# microlab.net
KiCad netlist of a schematic drawn in Altium Designer
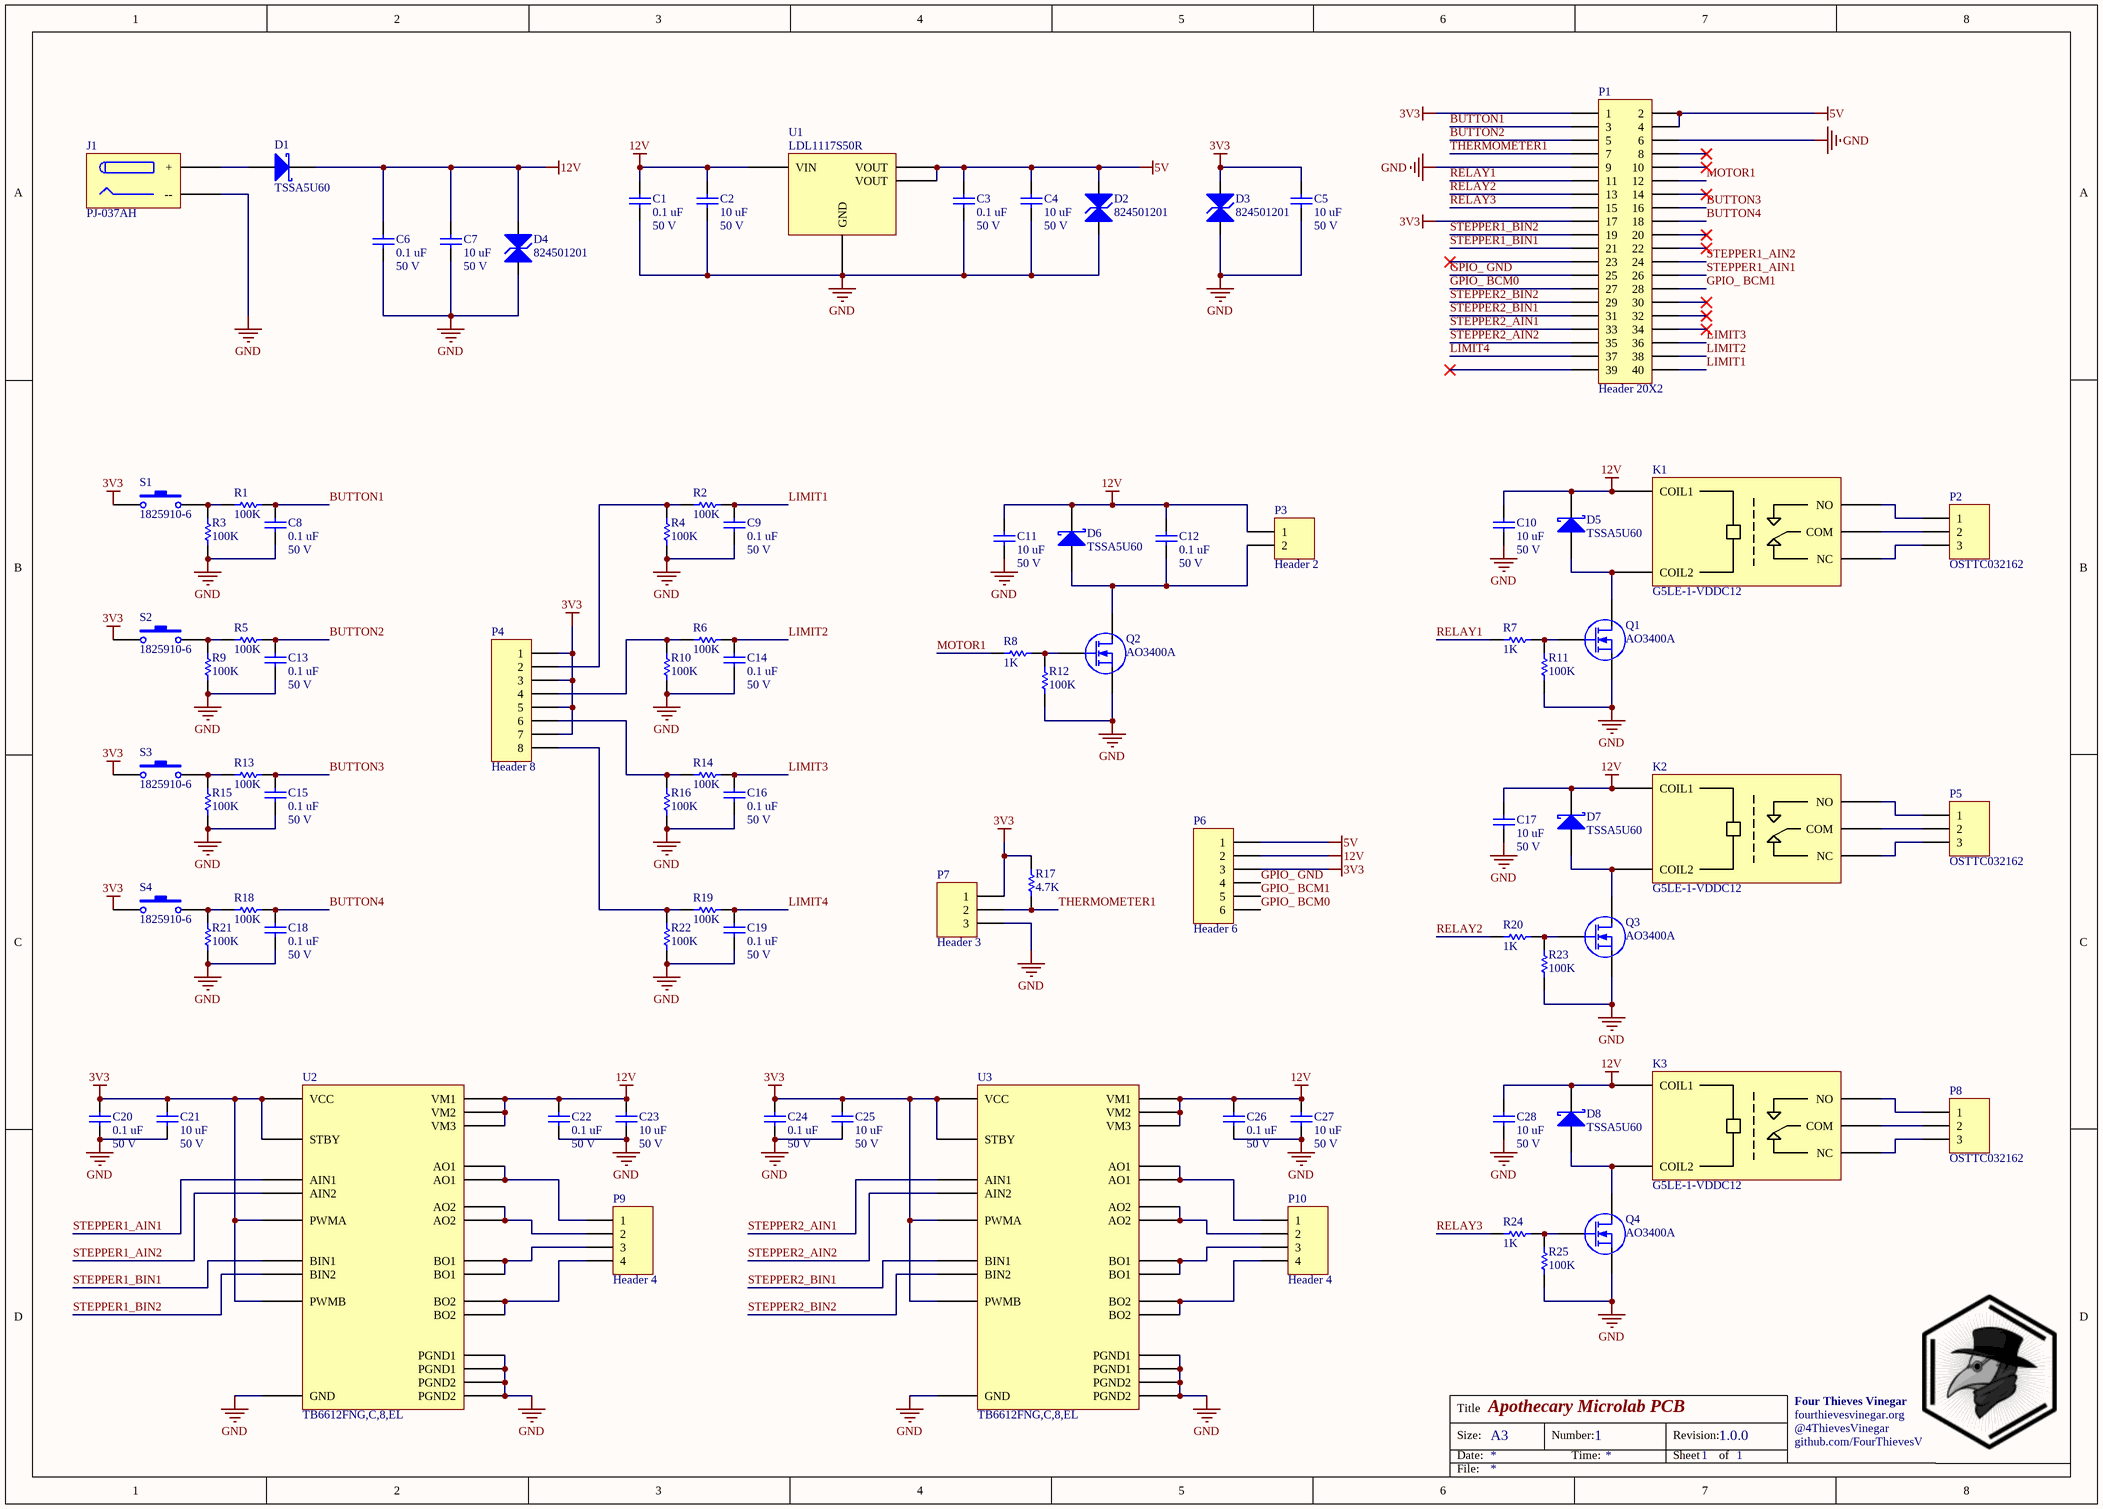
[diagram p0: microlab.SchDoc]

(export (version "E")
  (design (tool "Eeschema 10.0.6"))
  (components
    (comp (ref "C1")
      (value "0.1 uF")
      (footprint "1608[0603]")
      (description "Capacitor (Semiconductor SIM Model)")
      (fields (field (name "VOLTAGE") "50 V") (field (name "PUBLISHER") "Altium Limited"))
      (libsource (lib "Miscellaneous Devices") (part "Cap Semi"))
    )
    (comp (ref "C2")
      (value "10 uF")
      (footprint "C1206")
      (description "CL31A106KBHNNNE")
      (fields (field (name "VOLTAGE") "50 V") (field (name "PUBLISHER") "Altium Limited"))
      (libsource (lib "Miscellaneous Devices") (part "Cap Semi"))
    )
    (comp (ref "C3")
      (value "0.1 uF")
      (footprint "1608[0603]")
      (description "Capacitor (Semiconductor SIM Model)")
      (fields (field (name "VOLTAGE") "50 V") (field (name "PUBLISHER") "Altium Limited"))
      (libsource (lib "Miscellaneous Devices") (part "Cap Semi"))
    )
    (comp (ref "C4")
      (value "10 uF")
      (footprint "C1206")
      (description "CL31A106KBHNNNE")
      (fields (field (name "VOLTAGE") "50 V") (field (name "PUBLISHER") "Altium Limited"))
      (libsource (lib "Miscellaneous Devices") (part "Cap Semi"))
    )
    (comp (ref "C5")
      (value "10 uF")
      (footprint "C1206")
      (description "CL31A106KBHNNNE")
      (fields (field (name "VOLTAGE") "50 V") (field (name "PUBLISHER") "Altium Limited"))
      (libsource (lib "Miscellaneous Devices") (part "Cap Semi"))
    )
    (comp (ref "C6")
      (value "0.1 uF")
      (footprint "1608[0603]")
      (description "Capacitor (Semiconductor SIM Model)")
      (fields (field (name "VOLTAGE") "50 V") (field (name "PUBLISHER") "Altium Limited"))
      (libsource (lib "Miscellaneous Devices") (part "Cap Semi"))
    )
    (comp (ref "C7")
      (value "10 uF")
      (footprint "C1206")
      (description "CL31A106KBHNNNE")
      (fields (field (name "VOLTAGE") "50 V") (field (name "PUBLISHER") "Altium Limited"))
      (libsource (lib "Miscellaneous Devices") (part "Cap Semi"))
    )
    (comp (ref "C8")
      (value "0.1 uF")
      (footprint "1608[0603]")
      (description "Capacitor (Semiconductor SIM Model)")
      (fields (field (name "VOLTAGE") "50 V") (field (name "PUBLISHER") "Altium Limited"))
      (libsource (lib "Miscellaneous Devices") (part "Cap Semi"))
    )
    (comp (ref "C9")
      (value "0.1 uF")
      (footprint "1608[0603]")
      (description "Capacitor (Semiconductor SIM Model)")
      (fields (field (name "VOLTAGE") "50 V") (field (name "PUBLISHER") "Altium Limited"))
      (libsource (lib "Miscellaneous Devices") (part "Cap Semi"))
    )
    (comp (ref "C10")
      (value "10 uF")
      (footprint "C1206")
      (description "CL31A106KBHNNNE")
      (fields (field (name "VOLTAGE") "50 V") (field (name "PUBLISHER") "Altium Limited"))
      (libsource (lib "Miscellaneous Devices") (part "Cap Semi"))
    )
    (comp (ref "C11")
      (value "10 uF")
      (footprint "C1206")
      (description "CL31A106KBHNNNE")
      (fields (field (name "VOLTAGE") "50 V") (field (name "PUBLISHER") "Altium Limited"))
      (libsource (lib "Miscellaneous Devices") (part "Cap Semi"))
    )
    (comp (ref "C12")
      (value "0.1 uF")
      (footprint "1608[0603]")
      (description "Capacitor (Semiconductor SIM Model)")
      (fields (field (name "VOLTAGE") "50 V") (field (name "PUBLISHER") "Altium Limited"))
      (libsource (lib "Miscellaneous Devices") (part "Cap Semi"))
    )
    (comp (ref "C13")
      (value "0.1 uF")
      (footprint "1608[0603]")
      (description "Capacitor (Semiconductor SIM Model)")
      (fields (field (name "VOLTAGE") "50 V") (field (name "PUBLISHER") "Altium Limited"))
      (libsource (lib "Miscellaneous Devices") (part "Cap Semi"))
    )
    (comp (ref "C14")
      (value "0.1 uF")
      (footprint "1608[0603]")
      (description "Capacitor (Semiconductor SIM Model)")
      (fields (field (name "VOLTAGE") "50 V") (field (name "PUBLISHER") "Altium Limited"))
      (libsource (lib "Miscellaneous Devices") (part "Cap Semi"))
    )
    (comp (ref "C15")
      (value "0.1 uF")
      (footprint "1608[0603]")
      (description "Capacitor (Semiconductor SIM Model)")
      (fields (field (name "VOLTAGE") "50 V") (field (name "PUBLISHER") "Altium Limited"))
      (libsource (lib "Miscellaneous Devices") (part "Cap Semi"))
    )
    (comp (ref "C16")
      (value "0.1 uF")
      (footprint "1608[0603]")
      (description "Capacitor (Semiconductor SIM Model)")
      (fields (field (name "VOLTAGE") "50 V") (field (name "PUBLISHER") "Altium Limited"))
      (libsource (lib "Miscellaneous Devices") (part "Cap Semi"))
    )
    (comp (ref "C17")
      (value "10 uF")
      (footprint "C1206")
      (description "CL31A106KBHNNNE")
      (fields (field (name "VOLTAGE") "50 V") (field (name "PUBLISHER") "Altium Limited"))
      (libsource (lib "Miscellaneous Devices") (part "Cap Semi"))
    )
    (comp (ref "C18")
      (value "0.1 uF")
      (footprint "1608[0603]")
      (description "Capacitor (Semiconductor SIM Model)")
      (fields (field (name "VOLTAGE") "50 V") (field (name "PUBLISHER") "Altium Limited"))
      (libsource (lib "Miscellaneous Devices") (part "Cap Semi"))
    )
    (comp (ref "C19")
      (value "0.1 uF")
      (footprint "1608[0603]")
      (description "Capacitor (Semiconductor SIM Model)")
      (fields (field (name "VOLTAGE") "50 V") (field (name "PUBLISHER") "Altium Limited"))
      (libsource (lib "Miscellaneous Devices") (part "Cap Semi"))
    )
    (comp (ref "C20")
      (value "0.1 uF")
      (footprint "1608[0603]")
      (description "Capacitor (Semiconductor SIM Model)")
      (fields (field (name "VOLTAGE") "50 V") (field (name "PUBLISHER") "Altium Limited"))
      (libsource (lib "Miscellaneous Devices") (part "Cap Semi"))
    )
    (comp (ref "C21")
      (value "10 uF")
      (footprint "C1206")
      (description "CL31A106KBHNNNE")
      (fields (field (name "VOLTAGE") "50 V") (field (name "PUBLISHER") "Altium Limited"))
      (libsource (lib "Miscellaneous Devices") (part "Cap Semi"))
    )
    (comp (ref "C22")
      (value "0.1 uF")
      (footprint "1608[0603]")
      (description "Capacitor (Semiconductor SIM Model)")
      (fields (field (name "VOLTAGE") "50 V") (field (name "PUBLISHER") "Altium Limited"))
      (libsource (lib "Miscellaneous Devices") (part "Cap Semi"))
    )
    (comp (ref "C23")
      (value "10 uF")
      (footprint "C1206")
      (description "CL31A106KBHNNNE")
      (fields (field (name "VOLTAGE") "50 V") (field (name "PUBLISHER") "Altium Limited"))
      (libsource (lib "Miscellaneous Devices") (part "Cap Semi"))
    )
    (comp (ref "C24")
      (value "0.1 uF")
      (footprint "1608[0603]")
      (description "Capacitor (Semiconductor SIM Model)")
      (fields (field (name "VOLTAGE") "50 V") (field (name "PUBLISHER") "Altium Limited"))
      (libsource (lib "Miscellaneous Devices") (part "Cap Semi"))
    )
    (comp (ref "C25")
      (value "10 uF")
      (footprint "C1206")
      (description "CL31A106KBHNNNE")
      (fields (field (name "VOLTAGE") "50 V") (field (name "PUBLISHER") "Altium Limited"))
      (libsource (lib "Miscellaneous Devices") (part "Cap Semi"))
    )
    (comp (ref "C26")
      (value "0.1 uF")
      (footprint "1608[0603]")
      (description "Capacitor (Semiconductor SIM Model)")
      (fields (field (name "VOLTAGE") "50 V") (field (name "PUBLISHER") "Altium Limited"))
      (libsource (lib "Miscellaneous Devices") (part "Cap Semi"))
    )
    (comp (ref "C27")
      (value "10 uF")
      (footprint "C1206")
      (description "CL31A106KBHNNNE")
      (fields (field (name "VOLTAGE") "50 V") (field (name "PUBLISHER") "Altium Limited"))
      (libsource (lib "Miscellaneous Devices") (part "Cap Semi"))
    )
    (comp (ref "C28")
      (value "10 uF")
      (footprint "C1206")
      (description "CL31A106KBHNNNE")
      (fields (field (name "VOLTAGE") "50 V") (field (name "PUBLISHER") "Altium Limited"))
      (libsource (lib "Miscellaneous Devices") (part "Cap Semi"))
    )
    (comp (ref "D1")
      (value "TSSA5U60")
      (footprint "SMB")
      (description "Schottky Diode")
      (fields (field (name "PUBLISHER") "Altium Limited"))
      (libsource (lib "Miscellaneous Devices") (part "D Schottky"))
    )
    (comp (ref "D2")
      (value "824501201")
      (footprint "824501201")
      (description "TVS DIODE 20V 32.4V DO214AC")
      (libsource (lib "microlab") (part "824501201"))
    )
    (comp (ref "D3")
      (value "824501201")
      (footprint "824501201")
      (description "TVS DIODE 20V 32.4V DO214AC")
      (libsource (lib "microlab") (part "824501201"))
    )
    (comp (ref "D4")
      (value "824501201")
      (footprint "824501201")
      (description "TVS DIODE 20V 32.4V DO214AC")
      (libsource (lib "microlab") (part "824501201"))
    )
    (comp (ref "D5")
      (value "TSSA5U60")
      (footprint "SMB")
      (description "Schottky Diode")
      (fields (field (name "PUBLISHER") "Altium Limited"))
      (libsource (lib "Miscellaneous Devices") (part "D Schottky"))
    )
    (comp (ref "D6")
      (value "TSSA5U60")
      (footprint "SMB")
      (description "Schottky Diode")
      (fields (field (name "PUBLISHER") "Altium Limited"))
      (libsource (lib "Miscellaneous Devices") (part "D Schottky"))
    )
    (comp (ref "D7")
      (value "TSSA5U60")
      (footprint "SMB")
      (description "Schottky Diode")
      (fields (field (name "PUBLISHER") "Altium Limited"))
      (libsource (lib "Miscellaneous Devices") (part "D Schottky"))
    )
    (comp (ref "D8")
      (value "TSSA5U60")
      (footprint "SMB")
      (description "Schottky Diode")
      (fields (field (name "PUBLISHER") "Altium Limited"))
      (libsource (lib "Miscellaneous Devices") (part "D Schottky"))
    )
    (comp (ref "J1")
      (value "PJ-037AH")
      (footprint "PJ-037AH")
      (description "CONN PWR JACK 2X5.5MM SOLDER")
      (libsource (lib "microlab") (part "PJ-037AH"))
    )
    (comp (ref "K1")
      (value "G5LE-1-VDDC12")
      (footprint "G5LE-1-VDDC12")
      (description "RELAY GEN PURPOSE SPDT 10A 12V")
      (libsource (lib "microlab") (part "G5LE-1-VDDC12"))
    )
    (comp (ref "K2")
      (value "G5LE-1-VDDC12")
      (footprint "G5LE-1-VDDC12")
      (description "RELAY GEN PURPOSE SPDT 10A 12V")
      (libsource (lib "microlab") (part "G5LE-1-VDDC12"))
    )
    (comp (ref "K3")
      (value "G5LE-1-VDDC12")
      (footprint "G5LE-1-VDDC12")
      (description "RELAY GEN PURPOSE SPDT 10A 12V")
      (libsource (lib "microlab") (part "G5LE-1-VDDC12"))
    )
    (comp (ref "P1")
      (value "Header 20X2")
      (footprint "HDR2X20-centred")
      (description "Header, 20-Pin, Dual row")
      (fields (field (name "PUBLISHER") "Altium Limited"))
      (libsource (lib "Miscellaneous Connectors") (part "Header 20X2"))
    )
    (comp (ref "P2")
      (value "OSTTC032162")
      (footprint "OSTTC032162")
      (description "Header, 3-Pin")
      (fields (field (name "PUBLISHER") "Altium Limited"))
      (libsource (lib "Miscellaneous Connectors") (part "Header 3"))
    )
    (comp (ref "P3")
      (value "Header 2")
      (footprint "HDR1X2")
      (description "Header, 2-Pin")
      (fields (field (name "PUBLISHER") "Altium Limited"))
      (libsource (lib "Miscellaneous Connectors") (part "Header 2"))
    )
    (comp (ref "P4")
      (value "Header 8")
      (footprint "HDR1X8")
      (description "Header, 8-Pin")
      (fields (field (name "PUBLISHER") "Altium Limited"))
      (libsource (lib "Miscellaneous Connectors") (part "Header 8"))
    )
    (comp (ref "P5")
      (value "OSTTC032162")
      (footprint "OSTTC032162")
      (description "Header, 3-Pin")
      (fields (field (name "PUBLISHER") "Altium Limited"))
      (libsource (lib "Miscellaneous Connectors") (part "Header 3"))
    )
    (comp (ref "P6")
      (value "Header 6")
      (footprint "HDR1X6")
      (description "Header, 6-Pin")
      (fields (field (name "PUBLISHER") "Altium Limited"))
      (libsource (lib "Miscellaneous Connectors") (part "Header 6"))
    )
    (comp (ref "P7")
      (value "Header 3")
      (footprint "HDR1X3")
      (description "Header, 3-Pin")
      (fields (field (name "PUBLISHER") "Altium Limited"))
      (libsource (lib "") (part "Header 3_1"))
    )
    (comp (ref "P8")
      (value "OSTTC032162")
      (footprint "OSTTC032162")
      (description "Header, 3-Pin")
      (fields (field (name "PUBLISHER") "Altium Limited"))
      (libsource (lib "Miscellaneous Connectors") (part "Header 3"))
    )
    (comp (ref "P9")
      (value "Header 4")
      (footprint "HDR1X4")
      (description "Header, 4-Pin")
      (fields (field (name "PUBLISHER") "Altium Limited"))
      (libsource (lib "Miscellaneous Connectors") (part "Header 4"))
    )
    (comp (ref "P10")
      (value "Header 4")
      (footprint "HDR1X4")
      (description "Header, 4-Pin")
      (fields (field (name "PUBLISHER") "Altium Limited"))
      (libsource (lib "Miscellaneous Connectors") (part "Header 4"))
    )
    (comp (ref "Q1")
      (value "AO3400A")
      (footprint "AO3400A")
      (description "MOSFET N-CH 30V 5.7A SOT23")
      (libsource (lib "microlab") (part "AO3400A"))
    )
    (comp (ref "Q2")
      (value "AO3400A")
      (footprint "AO3400A")
      (description "MOSFET N-CH 30V 5.7A SOT23")
      (libsource (lib "microlab") (part "AO3400A"))
    )
    (comp (ref "Q3")
      (value "AO3400A")
      (footprint "AO3400A")
      (description "MOSFET N-CH 30V 5.7A SOT23")
      (libsource (lib "microlab") (part "AO3400A"))
    )
    (comp (ref "Q4")
      (value "AO3400A")
      (footprint "AO3400A")
      (description "MOSFET N-CH 30V 5.7A SOT23")
      (libsource (lib "microlab") (part "AO3400A"))
    )
    (comp (ref "R1")
      (value "100K")
      (footprint "J1-0603")
      (description "Resistor")
      (fields (field (name "PUBLISHER") "Altium Limited"))
      (libsource (lib "Miscellaneous Devices") (part "Res1"))
    )
    (comp (ref "R2")
      (value "100K")
      (footprint "J1-0603")
      (description "Resistor")
      (fields (field (name "PUBLISHER") "Altium Limited"))
      (libsource (lib "Miscellaneous Devices") (part "Res1"))
    )
    (comp (ref "R3")
      (value "100K")
      (footprint "J1-0603")
      (description "Resistor")
      (fields (field (name "PUBLISHER") "Altium Limited"))
      (libsource (lib "Miscellaneous Devices") (part "Res1"))
    )
    (comp (ref "R4")
      (value "100K")
      (footprint "J1-0603")
      (description "Resistor")
      (fields (field (name "PUBLISHER") "Altium Limited"))
      (libsource (lib "Miscellaneous Devices") (part "Res1"))
    )
    (comp (ref "R5")
      (value "100K")
      (footprint "J1-0603")
      (description "Resistor")
      (fields (field (name "PUBLISHER") "Altium Limited"))
      (libsource (lib "Miscellaneous Devices") (part "Res1"))
    )
    (comp (ref "R6")
      (value "100K")
      (footprint "J1-0603")
      (description "Resistor")
      (fields (field (name "PUBLISHER") "Altium Limited"))
      (libsource (lib "Miscellaneous Devices") (part "Res1"))
    )
    (comp (ref "R7")
      (value "1K")
      (footprint "J1-0603")
      (description "Resistor")
      (fields (field (name "PUBLISHER") "Altium Limited"))
      (libsource (lib "Miscellaneous Devices") (part "Res1"))
    )
    (comp (ref "R8")
      (value "1K")
      (footprint "J1-0603")
      (description "Resistor")
      (fields (field (name "PUBLISHER") "Altium Limited"))
      (libsource (lib "Miscellaneous Devices") (part "Res1"))
    )
    (comp (ref "R9")
      (value "100K")
      (footprint "J1-0603")
      (description "Resistor")
      (fields (field (name "PUBLISHER") "Altium Limited"))
      (libsource (lib "Miscellaneous Devices") (part "Res1"))
    )
    (comp (ref "R10")
      (value "100K")
      (footprint "J1-0603")
      (description "Resistor")
      (fields (field (name "PUBLISHER") "Altium Limited"))
      (libsource (lib "Miscellaneous Devices") (part "Res1"))
    )
    (comp (ref "R11")
      (value "100K")
      (footprint "J1-0603")
      (description "Resistor")
      (fields (field (name "PUBLISHER") "Altium Limited"))
      (libsource (lib "Miscellaneous Devices") (part "Res1"))
    )
    (comp (ref "R12")
      (value "100K")
      (footprint "J1-0603")
      (description "Resistor")
      (fields (field (name "PUBLISHER") "Altium Limited"))
      (libsource (lib "Miscellaneous Devices") (part "Res1"))
    )
    (comp (ref "R13")
      (value "100K")
      (footprint "J1-0603")
      (description "Resistor")
      (fields (field (name "PUBLISHER") "Altium Limited"))
      (libsource (lib "Miscellaneous Devices") (part "Res1"))
    )
    (comp (ref "R14")
      (value "100K")
      (footprint "J1-0603")
      (description "Resistor")
      (fields (field (name "PUBLISHER") "Altium Limited"))
      (libsource (lib "Miscellaneous Devices") (part "Res1"))
    )
    (comp (ref "R15")
      (value "100K")
      (footprint "J1-0603")
      (description "Resistor")
      (fields (field (name "PUBLISHER") "Altium Limited"))
      (libsource (lib "Miscellaneous Devices") (part "Res1"))
    )
    (comp (ref "R16")
      (value "100K")
      (footprint "J1-0603")
      (description "Resistor")
      (fields (field (name "PUBLISHER") "Altium Limited"))
      (libsource (lib "Miscellaneous Devices") (part "Res1"))
    )
    (comp (ref "R17")
      (value "4.7K")
      (footprint "J1-0603")
      (description "Resistor")
      (fields (field (name "PUBLISHER") "Altium Limited"))
      (libsource (lib "Miscellaneous Devices") (part "Res1"))
    )
    (comp (ref "R18")
      (value "100K")
      (footprint "J1-0603")
      (description "Resistor")
      (fields (field (name "PUBLISHER") "Altium Limited"))
      (libsource (lib "Miscellaneous Devices") (part "Res1"))
    )
    (comp (ref "R19")
      (value "100K")
      (footprint "J1-0603")
      (description "Resistor")
      (fields (field (name "PUBLISHER") "Altium Limited"))
      (libsource (lib "Miscellaneous Devices") (part "Res1"))
    )
    (comp (ref "R20")
      (value "1K")
      (footprint "J1-0603")
      (description "Resistor")
      (fields (field (name "PUBLISHER") "Altium Limited"))
      (libsource (lib "Miscellaneous Devices") (part "Res1"))
    )
    (comp (ref "R21")
      (value "100K")
      (footprint "J1-0603")
      (description "Resistor")
      (fields (field (name "PUBLISHER") "Altium Limited"))
      (libsource (lib "Miscellaneous Devices") (part "Res1"))
    )
    (comp (ref "R22")
      (value "100K")
      (footprint "J1-0603")
      (description "Resistor")
      (fields (field (name "PUBLISHER") "Altium Limited"))
      (libsource (lib "Miscellaneous Devices") (part "Res1"))
    )
    (comp (ref "R23")
      (value "100K")
      (footprint "J1-0603")
      (description "Resistor")
      (fields (field (name "PUBLISHER") "Altium Limited"))
      (libsource (lib "Miscellaneous Devices") (part "Res1"))
    )
    (comp (ref "R24")
      (value "1K")
      (footprint "J1-0603")
      (description "Resistor")
      (fields (field (name "PUBLISHER") "Altium Limited"))
      (libsource (lib "Miscellaneous Devices") (part "Res1"))
    )
    (comp (ref "R25")
      (value "100K")
      (footprint "J1-0603")
      (description "Resistor")
      (fields (field (name "PUBLISHER") "Altium Limited"))
      (libsource (lib "Miscellaneous Devices") (part "Res1"))
    )
    (comp (ref "S1")
      (value "1825910-6")
      (footprint "1825910-6")
      (description "SWITCH TACTILE SPST-NO 0.05A 24V")
      (fields (field (name "PUBLISHER") "Altium Limited"))
      (libsource (lib "Miscellaneous Devices") (part "SW-PB"))
    )
    (comp (ref "S2")
      (value "1825910-6")
      (footprint "1825910-6")
      (description "SWITCH TACTILE SPST-NO 0.05A 24V")
      (fields (field (name "PUBLISHER") "Altium Limited"))
      (libsource (lib "Miscellaneous Devices") (part "SW-PB"))
    )
    (comp (ref "S3")
      (value "1825910-6")
      (footprint "1825910-6")
      (description "SWITCH TACTILE SPST-NO 0.05A 24V")
      (fields (field (name "PUBLISHER") "Altium Limited"))
      (libsource (lib "Miscellaneous Devices") (part "SW-PB"))
    )
    (comp (ref "S4")
      (value "1825910-6")
      (footprint "1825910-6")
      (description "SWITCH TACTILE SPST-NO 0.05A 24V")
      (fields (field (name "PUBLISHER") "Altium Limited"))
      (libsource (lib "Miscellaneous Devices") (part "SW-PB"))
    )
    (comp (ref "U1")
      (value "LDL1117S50R")
      (footprint "LDL1117S50R")
      (description "IC REG LINEAR 5V 1.2A SOT223")
      (libsource (lib "microlab") (part "LDL1117S50R"))
    )
    (comp (ref "U2")
      (value "TB6612FNG,C,8,EL")
      (footprint "TB6612FNG,C,8,EL")
      (description "IC MOTOR DRIVER PAR 24SSOP")
      (libsource (lib "microlab") (part "TB6612FNG,C,8,EL"))
    )
    (comp (ref "U3")
      (value "TB6612FNG,C,8,EL")
      (footprint "TB6612FNG,C,8,EL")
      (description "IC MOTOR DRIVER PAR 24SSOP")
      (libsource (lib "microlab") (part "TB6612FNG,C,8,EL"))
    )
  )
  (nets
    (net (code "1") (name "/BUTTON1") (class "Default")
      (node (ref "C8") (pin "2") (pinfunction "2_2") (pintype "passive"))
      (node (ref "P1") (pin "3") (pinfunction "3_3") (pintype "passive"))
      (node (ref "R1") (pin "1") (pinfunction "1_1") (pintype "passive"))
    )
    (net (code "2") (name "/BUTTON2") (class "Default")
      (node (ref "C13") (pin "2") (pinfunction "2_2") (pintype "passive"))
      (node (ref "P1") (pin "5") (pinfunction "5_5") (pintype "passive"))
      (node (ref "R5") (pin "1") (pinfunction "1_1") (pintype "passive"))
    )
    (net (code "3") (name "/BUTTON3") (class "Default")
      (node (ref "C15") (pin "2") (pinfunction "2_2") (pintype "passive"))
      (node (ref "P1") (pin "16") (pinfunction "16_16") (pintype "passive"))
      (node (ref "R13") (pin "1") (pinfunction "1_1") (pintype "passive"))
    )
    (net (code "4") (name "/BUTTON4") (class "Default")
      (node (ref "C18") (pin "2") (pinfunction "2_2") (pintype "passive"))
      (node (ref "P1") (pin "18") (pinfunction "18_18") (pintype "passive"))
      (node (ref "R18") (pin "1") (pinfunction "1_1") (pintype "passive"))
    )
    (net (code "5") (name "/GPIO_ BCM0") (class "Default")
      (node (ref "P1") (pin "27") (pinfunction "27_27") (pintype "passive"))
      (node (ref "P6") (pin "6") (pinfunction "6_6") (pintype "passive"))
    )
    (net (code "6") (name "/GPIO_ BCM1") (class "Default")
      (node (ref "P1") (pin "28") (pinfunction "28_28") (pintype "passive"))
      (node (ref "P6") (pin "5") (pinfunction "5_5") (pintype "passive"))
    )
    (net (code "7") (name "/GPIO_ GND") (class "Default")
      (node (ref "P1") (pin "25") (pinfunction "25_25") (pintype "passive"))
      (node (ref "P6") (pin "4") (pinfunction "4_4") (pintype "passive"))
    )
    (net (code "8") (name "/LIMIT1") (class "Default")
      (node (ref "C9") (pin "2") (pinfunction "2_2") (pintype "passive"))
      (node (ref "P1") (pin "40") (pinfunction "40_40") (pintype "passive"))
      (node (ref "R2") (pin "1") (pinfunction "1_1") (pintype "passive"))
    )
    (net (code "9") (name "/LIMIT2") (class "Default")
      (node (ref "C14") (pin "2") (pinfunction "2_2") (pintype "passive"))
      (node (ref "P1") (pin "38") (pinfunction "38_38") (pintype "passive"))
      (node (ref "R6") (pin "1") (pinfunction "1_1") (pintype "passive"))
    )
    (net (code "10") (name "/LIMIT3") (class "Default")
      (node (ref "C16") (pin "2") (pinfunction "2_2") (pintype "passive"))
      (node (ref "P1") (pin "36") (pinfunction "36_36") (pintype "passive"))
      (node (ref "R14") (pin "1") (pinfunction "1_1") (pintype "passive"))
    )
    (net (code "11") (name "/LIMIT4") (class "Default")
      (node (ref "C19") (pin "2") (pinfunction "2_2") (pintype "passive"))
      (node (ref "P1") (pin "37") (pinfunction "37_37") (pintype "passive"))
      (node (ref "R19") (pin "1") (pinfunction "1_1") (pintype "passive"))
    )
    (net (code "12") (name "/MOTOR1") (class "Default")
      (node (ref "P1") (pin "12") (pinfunction "12_12") (pintype "passive"))
      (node (ref "R8") (pin "2") (pinfunction "2_2") (pintype "passive"))
    )
    (net (code "13") (name "/RELAY1") (class "Default")
      (node (ref "P1") (pin "11") (pinfunction "11_11") (pintype "passive"))
      (node (ref "R7") (pin "2") (pinfunction "2_2") (pintype "passive"))
    )
    (net (code "14") (name "/RELAY2") (class "Default")
      (node (ref "P1") (pin "13") (pinfunction "13_13") (pintype "passive"))
      (node (ref "R20") (pin "2") (pinfunction "2_2") (pintype "passive"))
    )
    (net (code "15") (name "/RELAY3") (class "Default")
      (node (ref "P1") (pin "15") (pinfunction "15_15") (pintype "passive"))
      (node (ref "R24") (pin "2") (pinfunction "2_2") (pintype "passive"))
    )
    (net (code "16") (name "/STEPPER1_AIN1") (class "Default")
      (node (ref "P1") (pin "26") (pinfunction "26_26") (pintype "passive"))
      (node (ref "U2") (pin "21") (pinfunction "AIN1_21") (pintype "passive"))
    )
    (net (code "17") (name "/STEPPER1_AIN2") (class "Default")
      (node (ref "P1") (pin "24") (pinfunction "24_24") (pintype "passive"))
      (node (ref "U2") (pin "22") (pinfunction "AIN2_22") (pintype "passive"))
    )
    (net (code "18") (name "/STEPPER1_BIN1") (class "Default")
      (node (ref "P1") (pin "21") (pinfunction "21_21") (pintype "passive"))
      (node (ref "U2") (pin "17") (pinfunction "BIN1_17") (pintype "passive"))
    )
    (net (code "19") (name "/STEPPER1_BIN2") (class "Default")
      (node (ref "P1") (pin "19") (pinfunction "19_19") (pintype "passive"))
      (node (ref "U2") (pin "16") (pinfunction "BIN2_16") (pintype "passive"))
    )
    (net (code "20") (name "/STEPPER2_AIN1") (class "Default")
      (node (ref "P1") (pin "33") (pinfunction "33_33") (pintype "passive"))
      (node (ref "U3") (pin "21") (pinfunction "AIN1_21") (pintype "passive"))
    )
    (net (code "21") (name "/STEPPER2_AIN2") (class "Default")
      (node (ref "P1") (pin "35") (pinfunction "35_35") (pintype "passive"))
      (node (ref "U3") (pin "22") (pinfunction "AIN2_22") (pintype "passive"))
    )
    (net (code "22") (name "/STEPPER2_BIN1") (class "Default")
      (node (ref "P1") (pin "31") (pinfunction "31_31") (pintype "passive"))
      (node (ref "U3") (pin "17") (pinfunction "BIN1_17") (pintype "passive"))
    )
    (net (code "23") (name "/STEPPER2_BIN2") (class "Default")
      (node (ref "P1") (pin "29") (pinfunction "29_29") (pintype "passive"))
      (node (ref "U3") (pin "16") (pinfunction "BIN2_16") (pintype "passive"))
    )
    (net (code "24") (name "/THERMOMETER1") (class "Default")
      (node (ref "P1") (pin "7") (pinfunction "7_7") (pintype "passive"))
      (node (ref "P7") (pin "2") (pinfunction "2_2") (pintype "passive"))
      (node (ref "R17") (pin "1") (pinfunction "1_1") (pintype "passive"))
    )
    (net (code "25") (name "3V3") (class "Default")
      (node (ref "C20") (pin "2") (pinfunction "2_2") (pintype "passive"))
      (node (ref "C21") (pin "2") (pinfunction "2_2") (pintype "passive"))
      (node (ref "C24") (pin "2") (pinfunction "2_2") (pintype "passive"))
      (node (ref "C25") (pin "2") (pinfunction "2_2") (pintype "passive"))
      (node (ref "C5") (pin "2") (pinfunction "2_2") (pintype "passive"))
      (node (ref "D3") (pin "2") (pinfunction "K_2") (pintype "passive"))
      (node (ref "P1") (pin "1") (pinfunction "1_1") (pintype "passive"))
      (node (ref "P1") (pin "17") (pinfunction "17_17") (pintype "passive"))
      (node (ref "P4") (pin "1") (pinfunction "1_1") (pintype "passive"))
      (node (ref "P4") (pin "3") (pinfunction "3_3") (pintype "passive"))
      (node (ref "P4") (pin "5") (pinfunction "5_5") (pintype "passive"))
      (node (ref "P4") (pin "7") (pinfunction "7_7") (pintype "passive"))
      (node (ref "P6") (pin "3") (pinfunction "3_3") (pintype "passive"))
      (node (ref "P7") (pin "1") (pinfunction "1_1") (pintype "passive"))
      (node (ref "R17") (pin "2") (pinfunction "2_2") (pintype "passive"))
      (node (ref "S1") (pin "1") (pinfunction "1_1") (pintype "passive"))
      (node (ref "S2") (pin "1") (pinfunction "1_1") (pintype "passive"))
      (node (ref "S3") (pin "1") (pinfunction "1_1") (pintype "passive"))
      (node (ref "S4") (pin "1") (pinfunction "1_1") (pintype "passive"))
      (node (ref "U2") (pin "15") (pinfunction "PWMB_15") (pintype "passive"))
      (node (ref "U2") (pin "19") (pinfunction "STBY_19") (pintype "passive"))
      (node (ref "U2") (pin "20") (pinfunction "VCC_20") (pintype "passive"))
      (node (ref "U2") (pin "23") (pinfunction "PWMA_23") (pintype "passive"))
      (node (ref "U3") (pin "15") (pinfunction "PWMB_15") (pintype "passive"))
      (node (ref "U3") (pin "19") (pinfunction "STBY_19") (pintype "passive"))
      (node (ref "U3") (pin "20") (pinfunction "VCC_20") (pintype "passive"))
      (node (ref "U3") (pin "23") (pinfunction "PWMA_23") (pintype "passive"))
    )
    (net (code "26") (name "5V") (class "Default")
      (node (ref "C3") (pin "2") (pinfunction "2_2") (pintype "passive"))
      (node (ref "C4") (pin "2") (pinfunction "2_2") (pintype "passive"))
      (node (ref "D2") (pin "2") (pinfunction "K_2") (pintype "passive"))
      (node (ref "P1") (pin "2") (pinfunction "2_2") (pintype "passive"))
      (node (ref "P1") (pin "4") (pinfunction "4_4") (pintype "passive"))
      (node (ref "P6") (pin "1") (pinfunction "1_1") (pintype "passive"))
      (node (ref "U1") (pin "2") (pinfunction "VOUT_2") (pintype "passive"))
      (node (ref "U1") (pin "4") (pinfunction "VOUT_4") (pintype "passive"))
    )
    (net (code "27") (name "12V") (class "Default")
      (node (ref "C1") (pin "2") (pinfunction "2_2") (pintype "passive"))
      (node (ref "C10") (pin "2") (pinfunction "2_2") (pintype "passive"))
      (node (ref "C11") (pin "2") (pinfunction "2_2") (pintype "passive"))
      (node (ref "C12") (pin "2") (pinfunction "2_2") (pintype "passive"))
      (node (ref "C17") (pin "2") (pinfunction "2_2") (pintype "passive"))
      (node (ref "C2") (pin "2") (pinfunction "2_2") (pintype "passive"))
      (node (ref "C22") (pin "2") (pinfunction "2_2") (pintype "passive"))
      (node (ref "C23") (pin "2") (pinfunction "2_2") (pintype "passive"))
      (node (ref "C26") (pin "2") (pinfunction "2_2") (pintype "passive"))
      (node (ref "C27") (pin "2") (pinfunction "2_2") (pintype "passive"))
      (node (ref "C28") (pin "2") (pinfunction "2_2") (pintype "passive"))
      (node (ref "C6") (pin "2") (pinfunction "2_2") (pintype "passive"))
      (node (ref "C7") (pin "2") (pinfunction "2_2") (pintype "passive"))
      (node (ref "D1") (pin "2") (pinfunction "K_2") (pintype "passive"))
      (node (ref "D4") (pin "2") (pinfunction "K_2") (pintype "passive"))
      (node (ref "D5") (pin "2") (pinfunction "K_2") (pintype "passive"))
      (node (ref "D6") (pin "2") (pinfunction "K_2") (pintype "passive"))
      (node (ref "D7") (pin "2") (pinfunction "K_2") (pintype "passive"))
      (node (ref "D8") (pin "2") (pinfunction "K_2") (pintype "passive"))
      (node (ref "K1") (pin "2") (pinfunction "COIL1_2") (pintype "passive"))
      (node (ref "K2") (pin "2") (pinfunction "COIL1_2") (pintype "passive"))
      (node (ref "K3") (pin "2") (pinfunction "COIL1_2") (pintype "passive"))
      (node (ref "P3") (pin "1") (pinfunction "1_1") (pintype "passive"))
      (node (ref "P6") (pin "2") (pinfunction "2_2") (pintype "passive"))
      (node (ref "U1") (pin "3") (pinfunction "VIN_3") (pintype "passive"))
      (node (ref "U2") (pin "13") (pinfunction "VM2_13") (pintype "passive"))
      (node (ref "U2") (pin "14") (pinfunction "VM3_14") (pintype "passive"))
      (node (ref "U2") (pin "24") (pinfunction "VM1_24") (pintype "passive"))
      (node (ref "U3") (pin "13") (pinfunction "VM2_13") (pintype "passive"))
      (node (ref "U3") (pin "14") (pinfunction "VM3_14") (pintype "passive"))
      (node (ref "U3") (pin "24") (pinfunction "VM1_24") (pintype "passive"))
    )
    (net (code "28") (name "GND") (class "Default")
      (node (ref "C1") (pin "1") (pinfunction "1_1") (pintype "passive"))
      (node (ref "C10") (pin "1") (pinfunction "1_1") (pintype "passive"))
      (node (ref "C11") (pin "1") (pinfunction "1_1") (pintype "passive"))
      (node (ref "C13") (pin "1") (pinfunction "1_1") (pintype "passive"))
      (node (ref "C14") (pin "1") (pinfunction "1_1") (pintype "passive"))
      (node (ref "C15") (pin "1") (pinfunction "1_1") (pintype "passive"))
      (node (ref "C16") (pin "1") (pinfunction "1_1") (pintype "passive"))
      (node (ref "C17") (pin "1") (pinfunction "1_1") (pintype "passive"))
      (node (ref "C18") (pin "1") (pinfunction "1_1") (pintype "passive"))
      (node (ref "C19") (pin "1") (pinfunction "1_1") (pintype "passive"))
      (node (ref "C2") (pin "1") (pinfunction "1_1") (pintype "passive"))
      (node (ref "C20") (pin "1") (pinfunction "1_1") (pintype "passive"))
      (node (ref "C21") (pin "1") (pinfunction "1_1") (pintype "passive"))
      (node (ref "C22") (pin "1") (pinfunction "1_1") (pintype "passive"))
      (node (ref "C23") (pin "1") (pinfunction "1_1") (pintype "passive"))
      (node (ref "C24") (pin "1") (pinfunction "1_1") (pintype "passive"))
      (node (ref "C25") (pin "1") (pinfunction "1_1") (pintype "passive"))
      (node (ref "C26") (pin "1") (pinfunction "1_1") (pintype "passive"))
      (node (ref "C27") (pin "1") (pinfunction "1_1") (pintype "passive"))
      (node (ref "C28") (pin "1") (pinfunction "1_1") (pintype "passive"))
      (node (ref "C3") (pin "1") (pinfunction "1_1") (pintype "passive"))
      (node (ref "C4") (pin "1") (pinfunction "1_1") (pintype "passive"))
      (node (ref "C5") (pin "1") (pinfunction "1_1") (pintype "passive"))
      (node (ref "C6") (pin "1") (pinfunction "1_1") (pintype "passive"))
      (node (ref "C7") (pin "1") (pinfunction "1_1") (pintype "passive"))
      (node (ref "C8") (pin "1") (pinfunction "1_1") (pintype "passive"))
      (node (ref "C9") (pin "1") (pinfunction "1_1") (pintype "passive"))
      (node (ref "D2") (pin "1") (pinfunction "A_1") (pintype "passive"))
      (node (ref "D3") (pin "1") (pinfunction "A_1") (pintype "passive"))
      (node (ref "D4") (pin "1") (pinfunction "A_1") (pintype "passive"))
      (node (ref "J1") (pin "2") (pinfunction "--_2") (pintype "passive"))
      (node (ref "P1") (pin "6") (pinfunction "6_6") (pintype "passive"))
      (node (ref "P1") (pin "9") (pinfunction "9_9") (pintype "passive"))
      (node (ref "P7") (pin "3") (pinfunction "3_3") (pintype "passive"))
      (node (ref "Q1") (pin "S") (pinfunction "S_S") (pintype "passive"))
      (node (ref "Q2") (pin "S") (pinfunction "S_S") (pintype "passive"))
      (node (ref "Q3") (pin "S") (pinfunction "S_S") (pintype "passive"))
      (node (ref "Q4") (pin "S") (pinfunction "S_S") (pintype "passive"))
      (node (ref "R10") (pin "1") (pinfunction "1_1") (pintype "passive"))
      (node (ref "R11") (pin "1") (pinfunction "1_1") (pintype "passive"))
      (node (ref "R12") (pin "1") (pinfunction "1_1") (pintype "passive"))
      (node (ref "R15") (pin "1") (pinfunction "1_1") (pintype "passive"))
      (node (ref "R16") (pin "1") (pinfunction "1_1") (pintype "passive"))
      (node (ref "R21") (pin "1") (pinfunction "1_1") (pintype "passive"))
      (node (ref "R22") (pin "1") (pinfunction "1_1") (pintype "passive"))
      (node (ref "R23") (pin "1") (pinfunction "1_1") (pintype "passive"))
      (node (ref "R25") (pin "1") (pinfunction "1_1") (pintype "passive"))
      (node (ref "R3") (pin "1") (pinfunction "1_1") (pintype "passive"))
      (node (ref "R4") (pin "1") (pinfunction "1_1") (pintype "passive"))
      (node (ref "R9") (pin "1") (pinfunction "1_1") (pintype "passive"))
      (node (ref "U1") (pin "1") (pinfunction "GND_1") (pintype "passive"))
      (node (ref "U2") (pin "10") (pinfunction "PGND2_10") (pintype "passive"))
      (node (ref "U2") (pin "18") (pinfunction "GND_18") (pintype "passive"))
      (node (ref "U2") (pin "3") (pinfunction "PGND1_3") (pintype "passive"))
      (node (ref "U2") (pin "4") (pinfunction "PGND1_4") (pintype "passive"))
      (node (ref "U2") (pin "9") (pinfunction "PGND2_9") (pintype "passive"))
      (node (ref "U3") (pin "10") (pinfunction "PGND2_10") (pintype "passive"))
      (node (ref "U3") (pin "18") (pinfunction "GND_18") (pintype "passive"))
      (node (ref "U3") (pin "3") (pinfunction "PGND1_3") (pintype "passive"))
      (node (ref "U3") (pin "4") (pinfunction "PGND1_4") (pintype "passive"))
      (node (ref "U3") (pin "9") (pinfunction "PGND2_9") (pintype "passive"))
    )
    (net (code "29") (name "Net-(D1-A)") (class "Default")
      (node (ref "D1") (pin "1") (pinfunction "A_1") (pintype "passive"))
      (node (ref "J1") (pin "1") (pinfunction "+_1") (pintype "passive"))
    )
    (net (code "30") (name "Net-(D5-A)") (class "Default")
      (node (ref "D5") (pin "1") (pinfunction "A_1") (pintype "passive"))
      (node (ref "K1") (pin "5") (pinfunction "COIL2_5") (pintype "passive"))
      (node (ref "Q1") (pin "D") (pinfunction "D_D") (pintype "passive"))
    )
    (net (code "31") (name "Net-(D6-A)") (class "Default")
      (node (ref "C12") (pin "1") (pinfunction "1_1") (pintype "passive"))
      (node (ref "D6") (pin "1") (pinfunction "A_1") (pintype "passive"))
      (node (ref "P3") (pin "2") (pinfunction "2_2") (pintype "passive"))
      (node (ref "Q2") (pin "D") (pinfunction "D_D") (pintype "passive"))
    )
    (net (code "32") (name "Net-(D7-A)") (class "Default")
      (node (ref "D7") (pin "1") (pinfunction "A_1") (pintype "passive"))
      (node (ref "K2") (pin "5") (pinfunction "COIL2_5") (pintype "passive"))
      (node (ref "Q3") (pin "D") (pinfunction "D_D") (pintype "passive"))
    )
    (net (code "33") (name "Net-(D8-A)") (class "Default")
      (node (ref "D8") (pin "1") (pinfunction "A_1") (pintype "passive"))
      (node (ref "K3") (pin "5") (pinfunction "COIL2_5") (pintype "passive"))
      (node (ref "Q4") (pin "D") (pinfunction "D_D") (pintype "passive"))
    )
    (net (code "34") (name "Net-(K1-COM)") (class "Default")
      (node (ref "K1") (pin "1") (pinfunction "COM_1") (pintype "passive"))
      (node (ref "P2") (pin "2") (pinfunction "2_2") (pintype "passive"))
    )
    (net (code "35") (name "Net-(K1-NC)") (class "Default")
      (node (ref "K1") (pin "4") (pinfunction "NC_4") (pintype "passive"))
      (node (ref "P2") (pin "3") (pinfunction "3_3") (pintype "passive"))
    )
    (net (code "36") (name "Net-(K1-NO)") (class "Default")
      (node (ref "K1") (pin "3") (pinfunction "NO_3") (pintype "passive"))
      (node (ref "P2") (pin "1") (pinfunction "1_1") (pintype "passive"))
    )
    (net (code "37") (name "Net-(K2-COM)") (class "Default")
      (node (ref "K2") (pin "1") (pinfunction "COM_1") (pintype "passive"))
      (node (ref "P5") (pin "2") (pinfunction "2_2") (pintype "passive"))
    )
    (net (code "38") (name "Net-(K2-NC)") (class "Default")
      (node (ref "K2") (pin "4") (pinfunction "NC_4") (pintype "passive"))
      (node (ref "P5") (pin "3") (pinfunction "3_3") (pintype "passive"))
    )
    (net (code "39") (name "Net-(K2-NO)") (class "Default")
      (node (ref "K2") (pin "3") (pinfunction "NO_3") (pintype "passive"))
      (node (ref "P5") (pin "1") (pinfunction "1_1") (pintype "passive"))
    )
    (net (code "40") (name "Net-(K3-COM)") (class "Default")
      (node (ref "K3") (pin "1") (pinfunction "COM_1") (pintype "passive"))
      (node (ref "P8") (pin "2") (pinfunction "2_2") (pintype "passive"))
    )
    (net (code "41") (name "Net-(K3-NC)") (class "Default")
      (node (ref "K3") (pin "4") (pinfunction "NC_4") (pintype "passive"))
      (node (ref "P8") (pin "3") (pinfunction "3_3") (pintype "passive"))
    )
    (net (code "42") (name "Net-(K3-NO)") (class "Default")
      (node (ref "K3") (pin "3") (pinfunction "NO_3") (pintype "passive"))
      (node (ref "P8") (pin "1") (pinfunction "1_1") (pintype "passive"))
    )
    (net (code "43") (name "Net-(P4-Pad2)") (class "Default")
      (node (ref "P4") (pin "2") (pinfunction "2_2") (pintype "passive"))
      (node (ref "R2") (pin "2") (pinfunction "2_2") (pintype "passive"))
      (node (ref "R4") (pin "2") (pinfunction "2_2") (pintype "passive"))
    )
    (net (code "44") (name "Net-(P4-Pad4)") (class "Default")
      (node (ref "P4") (pin "4") (pinfunction "4_4") (pintype "passive"))
      (node (ref "R10") (pin "2") (pinfunction "2_2") (pintype "passive"))
      (node (ref "R6") (pin "2") (pinfunction "2_2") (pintype "passive"))
    )
    (net (code "45") (name "Net-(P4-Pad6)") (class "Default")
      (node (ref "P4") (pin "6") (pinfunction "6_6") (pintype "passive"))
      (node (ref "R14") (pin "2") (pinfunction "2_2") (pintype "passive"))
      (node (ref "R16") (pin "2") (pinfunction "2_2") (pintype "passive"))
    )
    (net (code "46") (name "Net-(P4-Pad8)") (class "Default")
      (node (ref "P4") (pin "8") (pinfunction "8_8") (pintype "passive"))
      (node (ref "R19") (pin "2") (pinfunction "2_2") (pintype "passive"))
      (node (ref "R22") (pin "2") (pinfunction "2_2") (pintype "passive"))
    )
    (net (code "47") (name "Net-(P9-Pad1)") (class "Default")
      (node (ref "P9") (pin "1") (pinfunction "1_1") (pintype "passive"))
      (node (ref "U2") (pin "1") (pinfunction "AO1_1") (pintype "passive"))
      (node (ref "U2") (pin "2") (pinfunction "AO1_2") (pintype "passive"))
    )
    (net (code "48") (name "Net-(P9-Pad2)") (class "Default")
      (node (ref "P9") (pin "2") (pinfunction "2_2") (pintype "passive"))
      (node (ref "U2") (pin "5") (pinfunction "AO2_5") (pintype "passive"))
      (node (ref "U2") (pin "6") (pinfunction "AO2_6") (pintype "passive"))
    )
    (net (code "49") (name "Net-(P9-Pad3)") (class "Default")
      (node (ref "P9") (pin "3") (pinfunction "3_3") (pintype "passive"))
      (node (ref "U2") (pin "11") (pinfunction "BO1_11") (pintype "passive"))
      (node (ref "U2") (pin "12") (pinfunction "BO1_12") (pintype "passive"))
    )
    (net (code "50") (name "Net-(P9-Pad4)") (class "Default")
      (node (ref "P9") (pin "4") (pinfunction "4_4") (pintype "passive"))
      (node (ref "U2") (pin "7") (pinfunction "BO2_7") (pintype "passive"))
      (node (ref "U2") (pin "8") (pinfunction "BO2_8") (pintype "passive"))
    )
    (net (code "51") (name "Net-(P10-Pad1)") (class "Default")
      (node (ref "P10") (pin "1") (pinfunction "1_1") (pintype "passive"))
      (node (ref "U3") (pin "1") (pinfunction "AO1_1") (pintype "passive"))
      (node (ref "U3") (pin "2") (pinfunction "AO1_2") (pintype "passive"))
    )
    (net (code "52") (name "Net-(P10-Pad2)") (class "Default")
      (node (ref "P10") (pin "2") (pinfunction "2_2") (pintype "passive"))
      (node (ref "U3") (pin "5") (pinfunction "AO2_5") (pintype "passive"))
      (node (ref "U3") (pin "6") (pinfunction "AO2_6") (pintype "passive"))
    )
    (net (code "53") (name "Net-(P10-Pad3)") (class "Default")
      (node (ref "P10") (pin "3") (pinfunction "3_3") (pintype "passive"))
      (node (ref "U3") (pin "11") (pinfunction "BO1_11") (pintype "passive"))
      (node (ref "U3") (pin "12") (pinfunction "BO1_12") (pintype "passive"))
    )
    (net (code "54") (name "Net-(P10-Pad4)") (class "Default")
      (node (ref "P10") (pin "4") (pinfunction "4_4") (pintype "passive"))
      (node (ref "U3") (pin "7") (pinfunction "BO2_7") (pintype "passive"))
      (node (ref "U3") (pin "8") (pinfunction "BO2_8") (pintype "passive"))
    )
    (net (code "55") (name "Net-(Q1-PadG)") (class "Default")
      (node (ref "Q1") (pin "G") (pinfunction "G_G") (pintype "passive"))
      (node (ref "R11") (pin "2") (pinfunction "2_2") (pintype "passive"))
      (node (ref "R7") (pin "1") (pinfunction "1_1") (pintype "passive"))
    )
    (net (code "56") (name "Net-(Q2-PadG)") (class "Default")
      (node (ref "Q2") (pin "G") (pinfunction "G_G") (pintype "passive"))
      (node (ref "R12") (pin "2") (pinfunction "2_2") (pintype "passive"))
      (node (ref "R8") (pin "1") (pinfunction "1_1") (pintype "passive"))
    )
    (net (code "57") (name "Net-(Q3-PadG)") (class "Default")
      (node (ref "Q3") (pin "G") (pinfunction "G_G") (pintype "passive"))
      (node (ref "R20") (pin "1") (pinfunction "1_1") (pintype "passive"))
      (node (ref "R23") (pin "2") (pinfunction "2_2") (pintype "passive"))
    )
    (net (code "58") (name "Net-(Q4-PadG)") (class "Default")
      (node (ref "Q4") (pin "G") (pinfunction "G_G") (pintype "passive"))
      (node (ref "R24") (pin "1") (pinfunction "1_1") (pintype "passive"))
      (node (ref "R25") (pin "2") (pinfunction "2_2") (pintype "passive"))
    )
    (net (code "59") (name "Net-(R1-Pad2)") (class "Default")
      (node (ref "R1") (pin "2") (pinfunction "2_2") (pintype "passive"))
      (node (ref "R3") (pin "2") (pinfunction "2_2") (pintype "passive"))
      (node (ref "S1") (pin "2") (pinfunction "2_2") (pintype "passive"))
    )
    (net (code "60") (name "Net-(R5-Pad2)") (class "Default")
      (node (ref "R5") (pin "2") (pinfunction "2_2") (pintype "passive"))
      (node (ref "R9") (pin "2") (pinfunction "2_2") (pintype "passive"))
      (node (ref "S2") (pin "2") (pinfunction "2_2") (pintype "passive"))
    )
    (net (code "61") (name "Net-(R13-Pad2)") (class "Default")
      (node (ref "R13") (pin "2") (pinfunction "2_2") (pintype "passive"))
      (node (ref "R15") (pin "2") (pinfunction "2_2") (pintype "passive"))
      (node (ref "S3") (pin "2") (pinfunction "2_2") (pintype "passive"))
    )
    (net (code "62") (name "Net-(R18-Pad2)") (class "Default")
      (node (ref "R18") (pin "2") (pinfunction "2_2") (pintype "passive"))
      (node (ref "R21") (pin "2") (pinfunction "2_2") (pintype "passive"))
      (node (ref "S4") (pin "2") (pinfunction "2_2") (pintype "passive"))
    )
    (net (code "63") (name "unconnected-(P1-Pad8)") (class "Default")
      (node (ref "P1") (pin "8") (pinfunction "8_8") (pintype "passive+no_connect"))
    )
    (net (code "64") (name "unconnected-(P1-Pad10)") (class "Default")
      (node (ref "P1") (pin "10") (pinfunction "10_10") (pintype "passive+no_connect"))
    )
    (net (code "65") (name "unconnected-(P1-Pad14)") (class "Default")
      (node (ref "P1") (pin "14") (pinfunction "14_14") (pintype "passive+no_connect"))
    )
    (net (code "66") (name "unconnected-(P1-Pad20)") (class "Default")
      (node (ref "P1") (pin "20") (pinfunction "20_20") (pintype "passive+no_connect"))
    )
    (net (code "67") (name "unconnected-(P1-Pad22)") (class "Default")
      (node (ref "P1") (pin "22") (pinfunction "22_22") (pintype "passive+no_connect"))
    )
    (net (code "68") (name "unconnected-(P1-Pad23)") (class "Default")
      (node (ref "P1") (pin "23") (pinfunction "23_23") (pintype "passive+no_connect"))
    )
    (net (code "69") (name "unconnected-(P1-Pad30)") (class "Default")
      (node (ref "P1") (pin "30") (pinfunction "30_30") (pintype "passive+no_connect"))
    )
    (net (code "70") (name "unconnected-(P1-Pad32)") (class "Default")
      (node (ref "P1") (pin "32") (pinfunction "32_32") (pintype "passive+no_connect"))
    )
    (net (code "71") (name "unconnected-(P1-Pad34)") (class "Default")
      (node (ref "P1") (pin "34") (pinfunction "34_34") (pintype "passive+no_connect"))
    )
    (net (code "72") (name "unconnected-(P1-Pad39)") (class "Default")
      (node (ref "P1") (pin "39") (pinfunction "39_39") (pintype "passive+no_connect"))
    )
  )
)
